# SCH_Smart-Irrigation-System_2026-05-28.net
KiCad netlist of a schematic drawn in EasyEDA
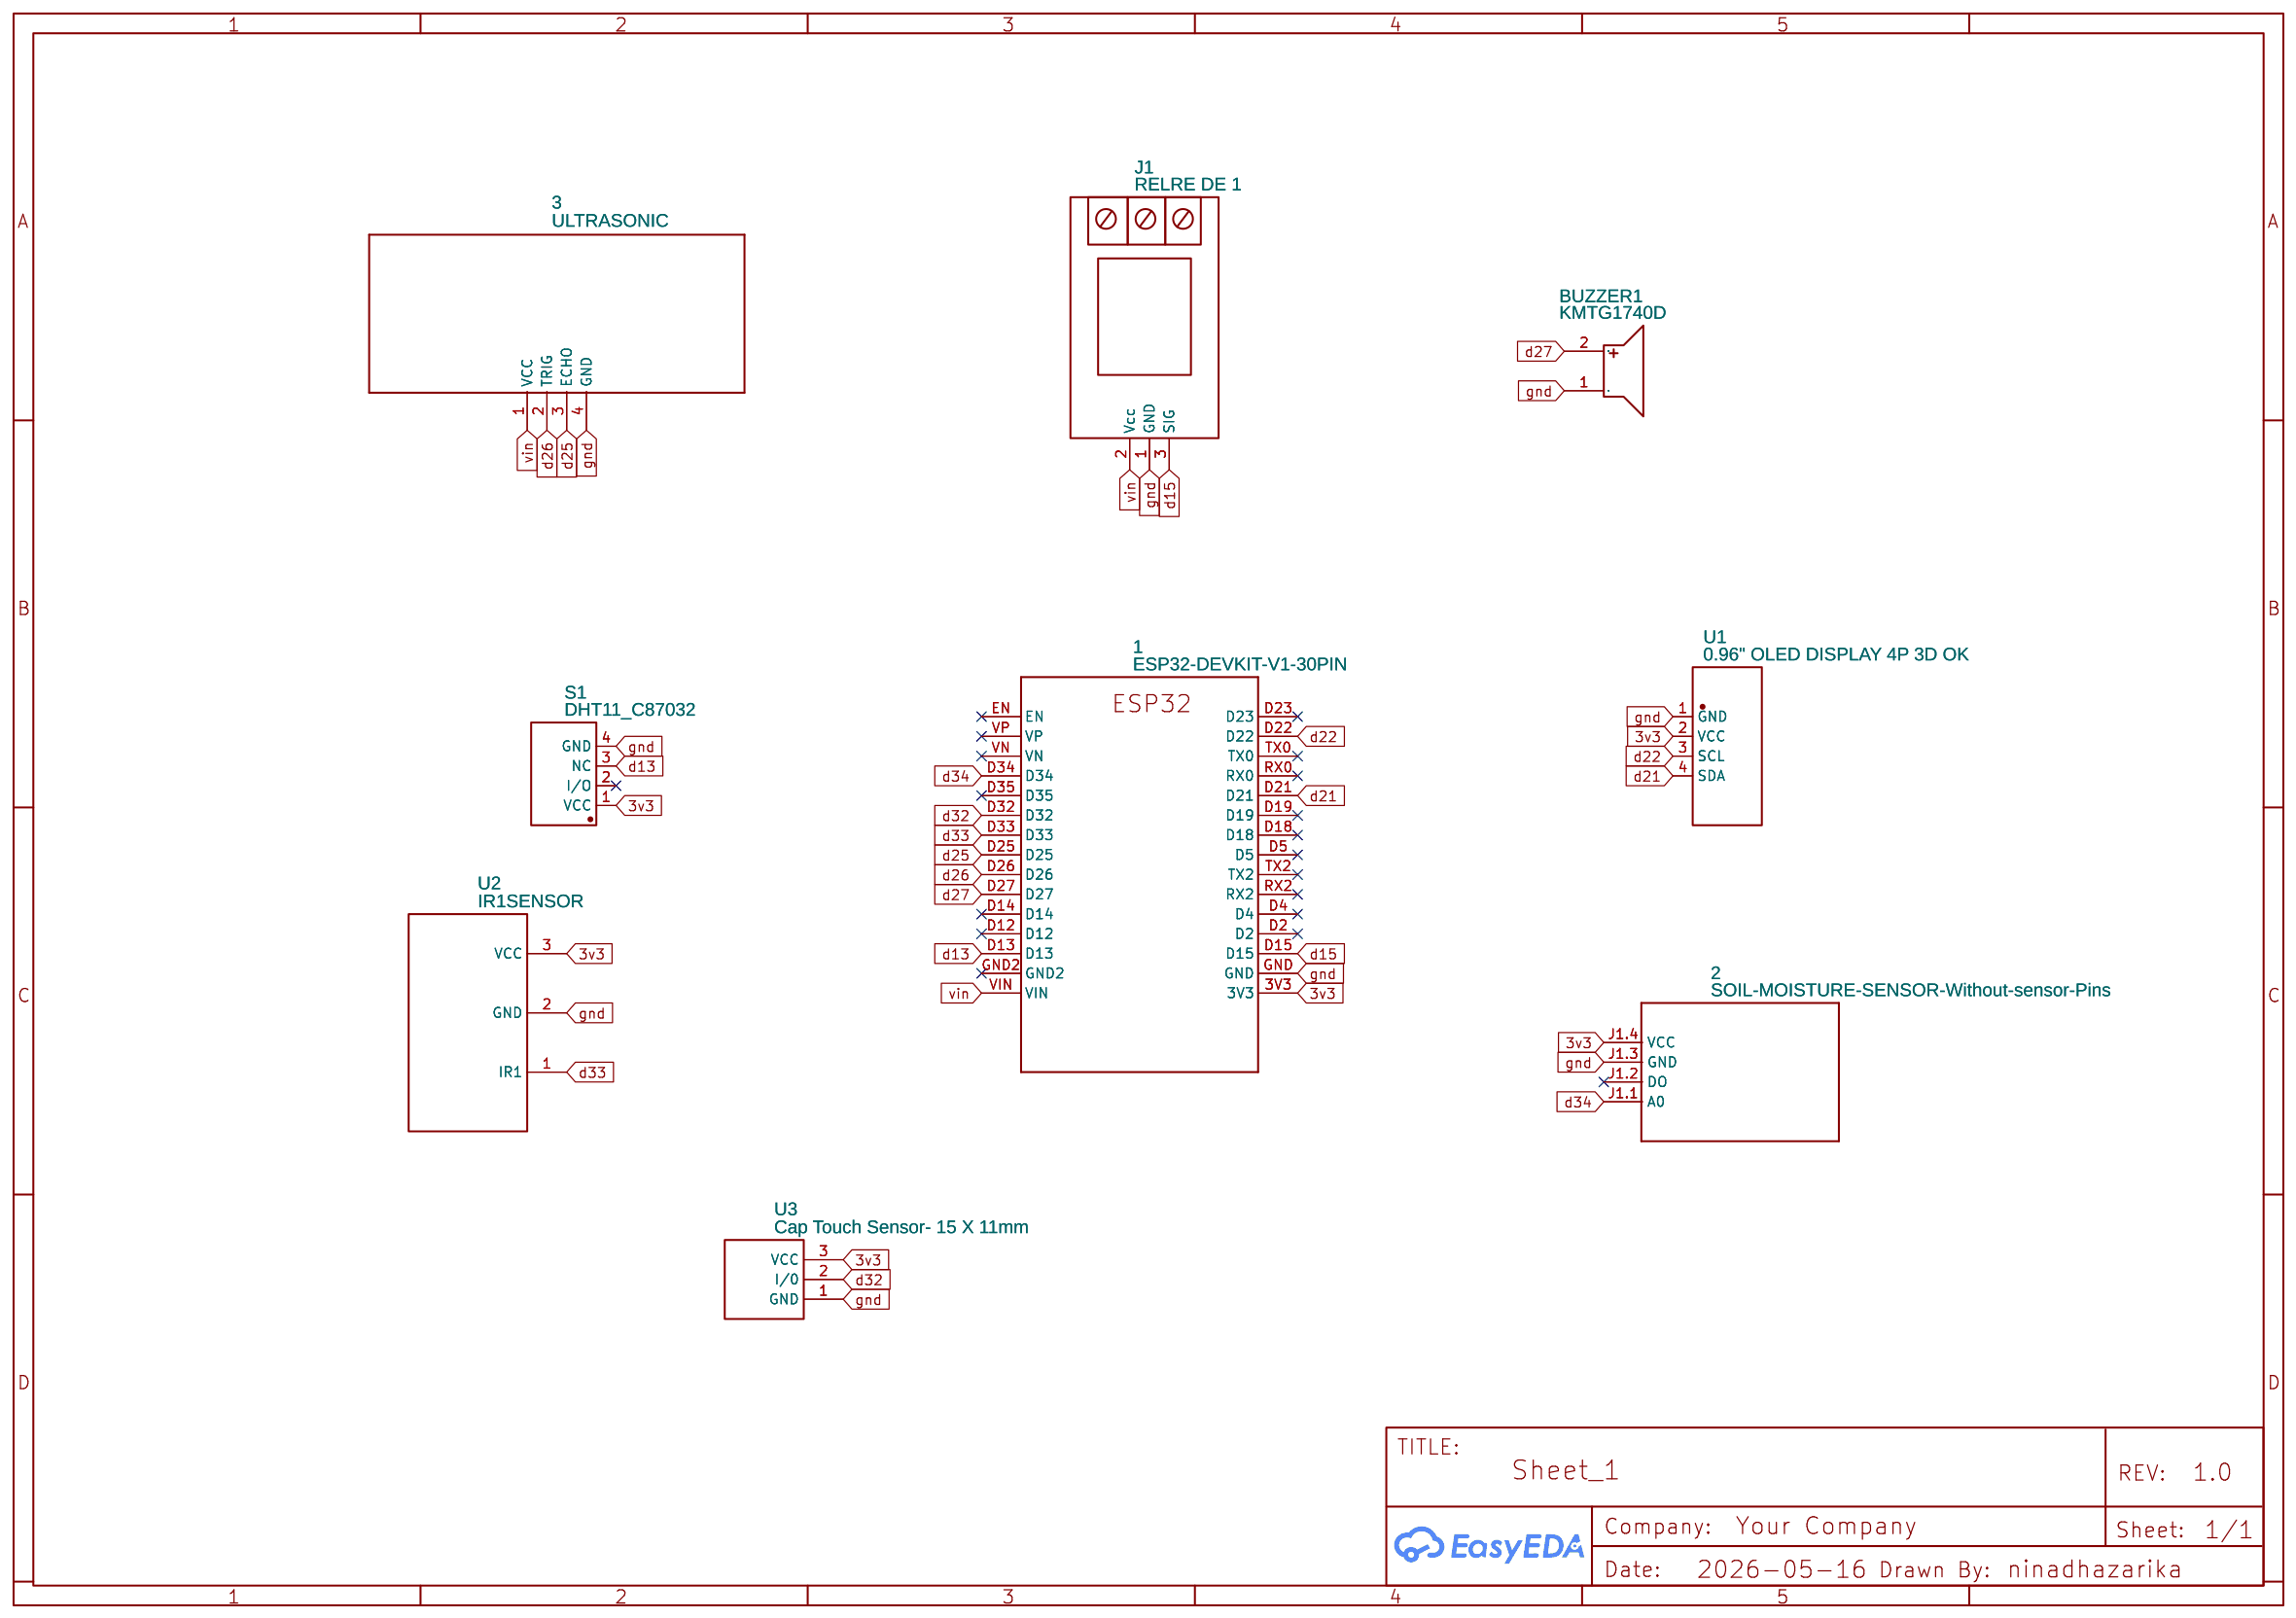
[diagram p0: schematic sheet]

(export (version "E")
  (design (tool "Eeschema 10.0.6"))
  (components
    (comp (ref "1") (value "ESP32-DEVKIT-V1-30PIN") (libsource (lib "") (part "ESP32-DEVKIT-V1-30PIN")))
    (comp (ref "2")
      (value "SOIL-MOISTURE-SENSOR-Without-sensor-Pins")
      (libsource (lib "") (part "SOIL-MOISTURE-SENSOR-Without-sensor-Pins"))
    )
    (comp (ref "3") (value "ULTRASONIC") (libsource (lib "") (part "ULTRASONIC")))
    (comp (ref "BUZZER1")
      (value "KMTG1740D")
      (fields (field (name "Manufacturer") "KINGSTATE(志丰电子)"))
      (libsource (lib "") (part "KMTG1740D"))
    )
    (comp (ref "J1")
      (value "RELRE DE 1")
      (fields (field (name "Manufacturer Part") "1-Channel 5V Relay Module w/ Opto-isolator"))
      (libsource (lib "") (part "RELRE DE 1"))
    )
    (comp (ref "S1")
      (value "DHT11_C87032")
      (fields (field (name "Manufacturer Part") "DHT11") (field (name "Manufacturer") "AOSONG"))
      (libsource (lib "") (part "DHT11_C87032"))
    )
    (comp (ref "U1")
      (value "0.96\" OLED DISPLAY 4P 3D OK")
      (fields
        (field (name "Manufacturer Part") "ZJY096S0700BG01蓝色")
        (field (name "Manufacturer") "郑州中景园电子技术有限公司")
      )
      (libsource (lib "") (part "0.96{dblquote} OLED DISPLAY 4P 3D OK"))
    )
    (comp (ref "U2") (value "IR1SENSOR") (libsource (lib "") (part "IR1SENSOR")))
    (comp (ref "U3")
      (value "Cap Touch Sensor- 15 X 11mm")
      (libsource (lib "") (part "Cap Touch Sensor- 15 X 11mm"))
    )
  )
  (nets
    (net (code "1") (name "3v3") (class "Default")
      (node (ref "1") (pin "3V3") (pinfunction "3V3_3V3") (pintype "unspecified"))
      (node (ref "2") (pin "J1.4") (pinfunction "VCC_J1.4") (pintype "unspecified"))
      (node (ref "S1") (pin "1") (pinfunction "VCC_1") (pintype "unspecified"))
      (node (ref "U1") (pin "2") (pinfunction "VCC_2") (pintype "unspecified"))
      (node (ref "U2") (pin "3") (pinfunction "VCC_3") (pintype "unspecified"))
      (node (ref "U3") (pin "3") (pinfunction "VCC_3") (pintype "unspecified"))
    )
    (net (code "2") (name "d13") (class "Default")
      (node (ref "1") (pin "D13") (pinfunction "D13_D13") (pintype "unspecified"))
      (node (ref "S1") (pin "3") (pinfunction "NC_3") (pintype "unspecified"))
    )
    (net (code "3") (name "d15") (class "Default")
      (node (ref "1") (pin "D15") (pinfunction "D15_D15") (pintype "unspecified"))
      (node (ref "J1") (pin "3") (pinfunction "SIG_3") (pintype "input"))
    )
    (net (code "4") (name "d21") (class "Default")
      (node (ref "1") (pin "D21") (pinfunction "D21_D21") (pintype "unspecified"))
      (node (ref "U1") (pin "4") (pinfunction "SDA_4") (pintype "unspecified"))
    )
    (net (code "5") (name "d22") (class "Default")
      (node (ref "1") (pin "D22") (pinfunction "D22_D22") (pintype "unspecified"))
      (node (ref "U1") (pin "3") (pinfunction "SCL_3") (pintype "unspecified"))
    )
    (net (code "6") (name "d25") (class "Default")
      (node (ref "1") (pin "D25") (pinfunction "D25_D25") (pintype "unspecified"))
      (node (ref "3") (pin "3") (pinfunction "ECHO_3") (pintype "bidirectional"))
    )
    (net (code "7") (name "d26") (class "Default")
      (node (ref "1") (pin "D26") (pinfunction "D26_D26") (pintype "unspecified"))
      (node (ref "3") (pin "2") (pinfunction "TRIG_2") (pintype "bidirectional"))
    )
    (net (code "8") (name "d27") (class "Default")
      (node (ref "1") (pin "D27") (pinfunction "D27_D27") (pintype "unspecified"))
      (node (ref "BUZZER1") (pin "2") (pinfunction "2_2") (pintype "unspecified"))
    )
    (net (code "9") (name "d32") (class "Default")
      (node (ref "1") (pin "D32") (pinfunction "D32_D32") (pintype "unspecified"))
      (node (ref "U3") (pin "2") (pinfunction "I/0_2") (pintype "unspecified"))
    )
    (net (code "10") (name "d33") (class "Default")
      (node (ref "1") (pin "D33") (pinfunction "D33_D33") (pintype "unspecified"))
      (node (ref "U2") (pin "1") (pinfunction "IR1_1") (pintype "unspecified"))
    )
    (net (code "11") (name "d34") (class "Default")
      (node (ref "1") (pin "D34") (pinfunction "D34_D34") (pintype "unspecified"))
      (node (ref "2") (pin "J1.1") (pinfunction "A0_J1.1") (pintype "unspecified"))
    )
    (net (code "12") (name "gnd") (class "Default")
      (node (ref "1") (pin "GND") (pinfunction "GND_GND") (pintype "unspecified"))
      (node (ref "2") (pin "J1.3") (pinfunction "GND_J1.3") (pintype "unspecified"))
      (node (ref "3") (pin "4") (pinfunction "GND_4") (pintype "bidirectional"))
      (node (ref "BUZZER1") (pin "1") (pinfunction "1_1") (pintype "unspecified"))
      (node (ref "J1") (pin "1") (pinfunction "GND_1") (pintype "input"))
      (node (ref "S1") (pin "4") (pinfunction "GND_4") (pintype "unspecified"))
      (node (ref "U1") (pin "1") (pinfunction "GND_1") (pintype "unspecified"))
      (node (ref "U2") (pin "2") (pinfunction "GND_2") (pintype "unspecified"))
      (node (ref "U3") (pin "1") (pinfunction "GND_1") (pintype "unspecified"))
    )
    (net (code "13") (name "unconnected-(1-PadD2)") (class "Default")
      (node (ref "1") (pin "D2") (pinfunction "D2_D2") (pintype "unspecified+no_connect"))
    )
    (net (code "14") (name "unconnected-(1-PadD4)") (class "Default")
      (node (ref "1") (pin "D4") (pinfunction "D4_D4") (pintype "unspecified+no_connect"))
    )
    (net (code "15") (name "unconnected-(1-PadD5)") (class "Default")
      (node (ref "1") (pin "D5") (pinfunction "D5_D5") (pintype "unspecified+no_connect"))
    )
    (net (code "16") (name "unconnected-(1-PadD12)") (class "Default")
      (node (ref "1") (pin "D12") (pinfunction "D12_D12") (pintype "unspecified+no_connect"))
    )
    (net (code "17") (name "unconnected-(1-PadD14)") (class "Default")
      (node (ref "1") (pin "D14") (pinfunction "D14_D14") (pintype "unspecified+no_connect"))
    )
    (net (code "18") (name "unconnected-(1-PadD18)") (class "Default")
      (node (ref "1") (pin "D18") (pinfunction "D18_D18") (pintype "unspecified+no_connect"))
    )
    (net (code "19") (name "unconnected-(1-PadD19)") (class "Default")
      (node (ref "1") (pin "D19") (pinfunction "D19_D19") (pintype "unspecified+no_connect"))
    )
    (net (code "20") (name "unconnected-(1-PadD23)") (class "Default")
      (node (ref "1") (pin "D23") (pinfunction "D23_D23") (pintype "unspecified+no_connect"))
    )
    (net (code "21") (name "unconnected-(1-PadD35)") (class "Default")
      (node (ref "1") (pin "D35") (pinfunction "D35_D35") (pintype "unspecified+no_connect"))
    )
    (net (code "22") (name "unconnected-(1-PadEN)") (class "Default")
      (node (ref "1") (pin "EN") (pinfunction "EN_EN") (pintype "unspecified+no_connect"))
    )
    (net (code "23") (name "unconnected-(1-PadGND2)") (class "Default")
      (node (ref "1") (pin "GND2") (pinfunction "GND2_GND2") (pintype "unspecified+no_connect"))
    )
    (net (code "24") (name "unconnected-(1-PadRX0)") (class "Default")
      (node (ref "1") (pin "RX0") (pinfunction "RX0_RX0") (pintype "unspecified+no_connect"))
    )
    (net (code "25") (name "unconnected-(1-PadRX2)") (class "Default")
      (node (ref "1") (pin "RX2") (pinfunction "RX2_RX2") (pintype "unspecified+no_connect"))
    )
    (net (code "26") (name "unconnected-(1-PadTX0)") (class "Default")
      (node (ref "1") (pin "TX0") (pinfunction "TX0_TX0") (pintype "unspecified+no_connect"))
    )
    (net (code "27") (name "unconnected-(1-PadTX2)") (class "Default")
      (node (ref "1") (pin "TX2") (pinfunction "TX2_TX2") (pintype "unspecified+no_connect"))
    )
    (net (code "28") (name "unconnected-(1-PadVN)") (class "Default")
      (node (ref "1") (pin "VN") (pinfunction "VN_VN") (pintype "unspecified+no_connect"))
    )
    (net (code "29") (name "unconnected-(1-PadVP)") (class "Default")
      (node (ref "1") (pin "VP") (pinfunction "VP_VP") (pintype "unspecified+no_connect"))
    )
    (net (code "30") (name "unconnected-(2-DO-PadJ1.2)") (class "Default")
      (node (ref "2") (pin "J1.2") (pinfunction "DO_J1.2") (pintype "unspecified+no_connect"))
    )
    (net (code "31") (name "unconnected-(S1-I{slash}O-Pad2)") (class "Default")
      (node (ref "S1") (pin "2") (pinfunction "I/O_2") (pintype "unspecified+no_connect"))
    )
    (net (code "32") (name "vin") (class "Default")
      (node (ref "1") (pin "VIN") (pinfunction "VIN_VIN") (pintype "unspecified"))
      (node (ref "3") (pin "1") (pinfunction "VCC_1") (pintype "bidirectional"))
      (node (ref "J1") (pin "2") (pinfunction "Vcc_2") (pintype "input"))
    )
  )
)
